# Modulo_Sensores.net
KiCad netlist of a schematic drawn in Altium Designer
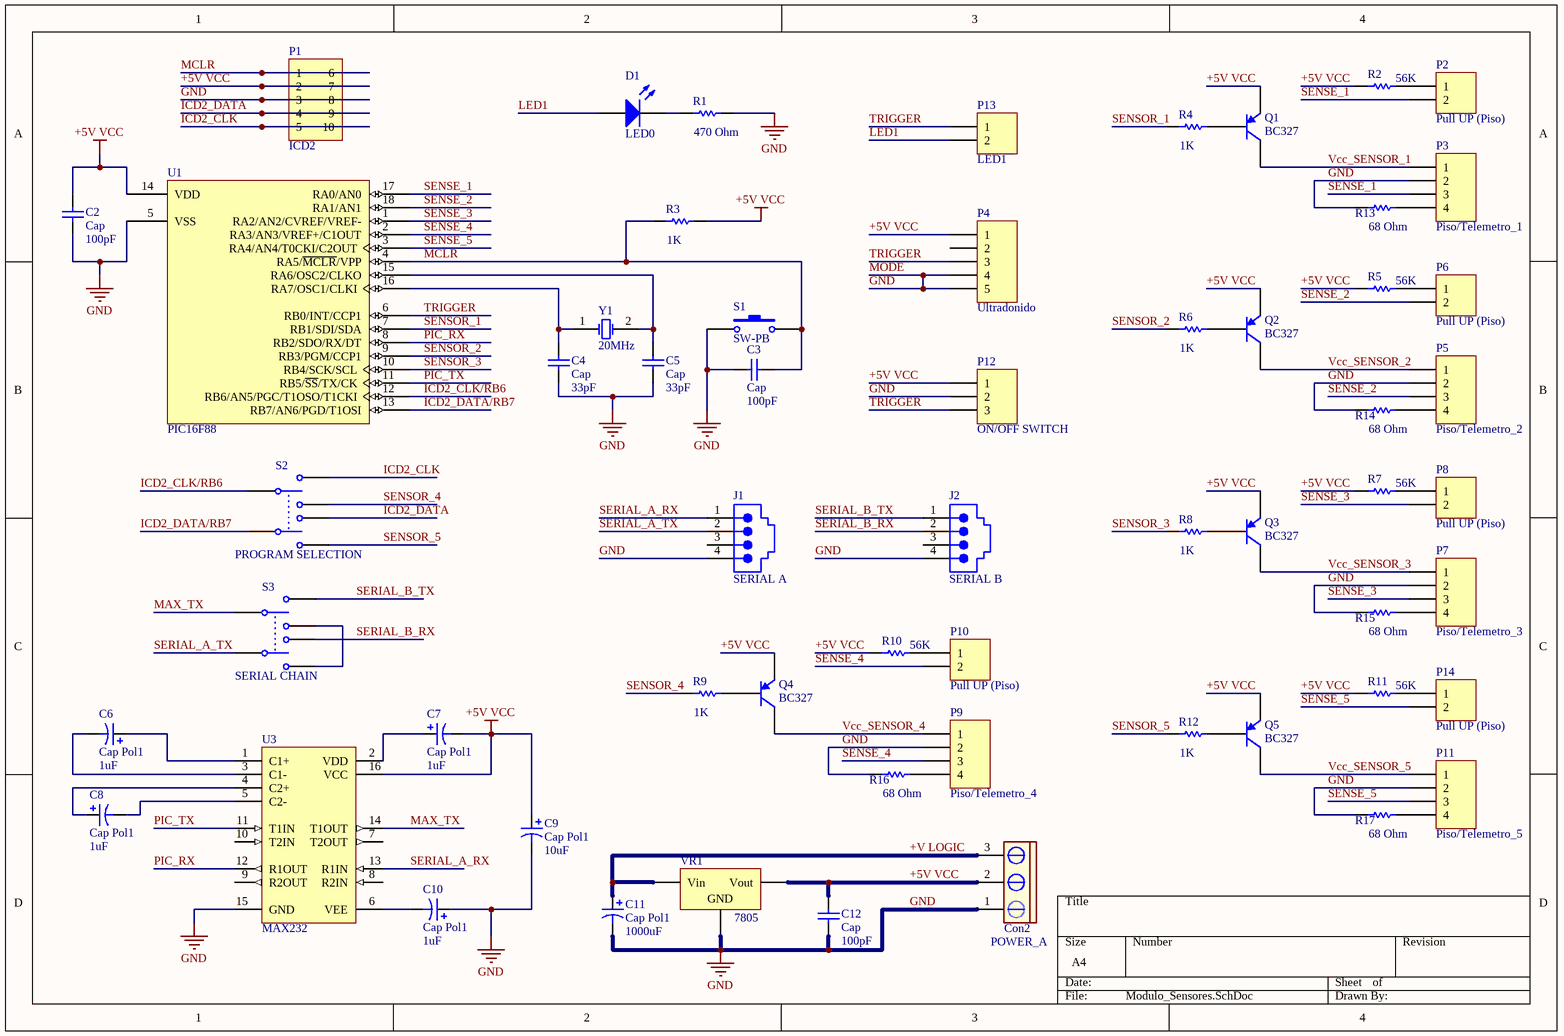
[diagram p0: Modulo_Sensores.SchDoc]

(export (version "E")
  (design (tool "Eeschema 10.0.6"))
  (components
    (comp (ref "C2")
      (value "Cap")
      (footprint "CAPR2.54-5.1x3.2")
      (description "Capacitor")
      (fields (field (name "ALTIUM_VALUE") "100pF") (field (name "PUBLISHER") "Altium Limited"))
      (libsource (lib "Miscellaneous Devices") (part "Cap"))
    )
    (comp (ref "C3")
      (value "Cap")
      (footprint "CAPR2.54-5.1x3.2")
      (description "Capacitor")
      (fields (field (name "ALTIUM_VALUE") "100pF") (field (name "PUBLISHER") "Altium Limited"))
      (libsource (lib "Miscellaneous Devices") (part "Cap"))
    )
    (comp (ref "C4")
      (value "Cap")
      (footprint "CAPR2.54-5.1x3.2")
      (description "Capacitor")
      (fields (field (name "ALTIUM_VALUE") "33pF") (field (name "PUBLISHER") "Altium Limited"))
      (libsource (lib "Miscellaneous Devices") (part "Cap"))
    )
    (comp (ref "C5")
      (value "Cap")
      (footprint "CAPR2.54-5.1x3.2")
      (description "Capacitor")
      (fields (field (name "ALTIUM_VALUE") "33pF") (field (name "PUBLISHER") "Altium Limited"))
      (libsource (lib "Miscellaneous Devices") (part "Cap"))
    )
    (comp (ref "C6")
      (value "Cap Pol1")
      (footprint "CAPPR2-5x6.8")
      (description "Polarized Capacitor (Radial)")
      (fields (field (name "ALTIUM_VALUE") "1uF") (field (name "PUBLISHER") "Altium Limited"))
      (libsource (lib "Miscellaneous Devices") (part "Cap Pol1"))
    )
    (comp (ref "C7")
      (value "Cap Pol1")
      (footprint "CAPPR2-5x6.8")
      (description "Polarized Capacitor (Radial)")
      (fields (field (name "ALTIUM_VALUE") "1uF") (field (name "PUBLISHER") "Altium Limited"))
      (libsource (lib "Miscellaneous Devices") (part "Cap Pol1"))
    )
    (comp (ref "C8")
      (value "Cap Pol1")
      (footprint "CAPPR2-5x6.8")
      (description "Polarized Capacitor (Radial)")
      (fields (field (name "ALTIUM_VALUE") "1uF") (field (name "PUBLISHER") "Altium Limited"))
      (libsource (lib "Miscellaneous Devices") (part "Cap Pol1"))
    )
    (comp (ref "C9")
      (value "Cap Pol1")
      (footprint "CAPPR2-5x6.8")
      (description "Polarized Capacitor (Radial)")
      (fields (field (name "ALTIUM_VALUE") "10uF") (field (name "PUBLISHER") "Altium Limited"))
      (libsource (lib "Miscellaneous Devices") (part "Cap Pol1"))
    )
    (comp (ref "C10")
      (value "Cap Pol1")
      (footprint "CAPPR2-5x6.8")
      (description "Polarized Capacitor (Radial)")
      (fields (field (name "ALTIUM_VALUE") "1uF") (field (name "PUBLISHER") "Altium Limited"))
      (libsource (lib "Miscellaneous Devices") (part "Cap Pol1"))
    )
    (comp (ref "C11")
      (value "Cap Pol1")
      (footprint "RB5-10.5")
      (description "Polarized Capacitor (Radial)")
      (fields (field (name "ALTIUM_VALUE") "1000uF") (field (name "PUBLISHER") "Altium Limited"))
      (libsource (lib "Miscellaneous Devices") (part "Cap Pol1"))
    )
    (comp (ref "C12")
      (value "Cap")
      (footprint "CAPR2.54-5.1x3.2")
      (description "Capacitor")
      (fields (field (name "ALTIUM_VALUE") "100pF") (field (name "PUBLISHER") "Altium Limited"))
      (libsource (lib "Miscellaneous Devices") (part "Cap"))
    )
    (comp (ref "Con2")
      (value "POWER_A")
      (footprint "My_CN3")
      (description "Connector green screw")
      (libsource (lib "Protel_Library") (part "CON3 pin Green"))
    )
    (comp (ref "D1")
      (value "LED0")
      (footprint "LED-0")
      (description "Typical INFRARED GaAs LED")
      (fields (field (name "PUBLISHER") "Altium Limited"))
      (libsource (lib "Miscellaneous Devices") (part "LED0"))
    )
    (comp (ref "J1")
      (value "SERIAL A")
      (footprint "15-43-6245")
      (description "Right Angle, Standard Profile, RJ45-Keyed, Flange Mount PCB Jack")
      (fields (field (name "PUBLISHER") "Altium Limited"))
      (libsource (lib "Molex Modular Jack Right Angle") (part "15-43-6245"))
    )
    (comp (ref "J2")
      (value "SERIAL B")
      (footprint "15-43-6245")
      (description "Right Angle, Standard Profile, RJ45-Keyed, Flange Mount PCB Jack")
      (fields (field (name "PUBLISHER") "Altium Limited"))
      (libsource (lib "Molex Modular Jack Right Angle") (part "15-43-6245"))
    )
    (comp (ref "P1")
      (value "ICD2")
      (footprint "HEADER10_5x2_B")
      (description "Header, 5-Pin, Dual row")
      (fields (field (name "PUBLISHER") "Altium Limited"))
      (libsource (lib "Miscellaneous Connectors") (part "Header 5X2A"))
    )
    (comp (ref "P2")
      (value "Pull UP (Piso)")
      (footprint "HDR1X2")
      (description "Header, 2-Pin")
      (fields (field (name "PUBLISHER") "Altium Limited"))
      (libsource (lib "Miscellaneous Connectors") (part "Header 2"))
    )
    (comp (ref "P3")
      (value "Piso/Telemetro_1")
      (footprint "HDR1X4")
      (description "Header, 4-Pin")
      (fields (field (name "PUBLISHER") "Altium Limited"))
      (libsource (lib "Miscellaneous Connectors") (part "Header 4"))
    )
    (comp (ref "P4")
      (value "Ultradonido")
      (footprint "HDR1X5")
      (description "Header, 5-Pin")
      (fields (field (name "PUBLISHER") "Altium Limited"))
      (libsource (lib "Miscellaneous Connectors") (part "Header 5"))
    )
    (comp (ref "P5")
      (value "Piso/Telemetro_2")
      (footprint "HDR1X4")
      (description "Header, 4-Pin")
      (fields (field (name "PUBLISHER") "Altium Limited"))
      (libsource (lib "Miscellaneous Connectors") (part "Header 4"))
    )
    (comp (ref "P6")
      (value "Pull UP (Piso)")
      (footprint "HDR1X2")
      (description "Header, 2-Pin")
      (fields (field (name "PUBLISHER") "Altium Limited"))
      (libsource (lib "Miscellaneous Connectors") (part "Header 2"))
    )
    (comp (ref "P7")
      (value "Piso/Telemetro_3")
      (footprint "HDR1X4")
      (description "Header, 4-Pin")
      (fields (field (name "PUBLISHER") "Altium Limited"))
      (libsource (lib "Miscellaneous Connectors") (part "Header 4"))
    )
    (comp (ref "P8")
      (value "Pull UP (Piso)")
      (footprint "HDR1X2")
      (description "Header, 2-Pin")
      (fields (field (name "PUBLISHER") "Altium Limited"))
      (libsource (lib "Miscellaneous Connectors") (part "Header 2"))
    )
    (comp (ref "P9")
      (value "Piso/Telemetro_4")
      (footprint "HDR1X4")
      (description "Header, 4-Pin")
      (fields (field (name "PUBLISHER") "Altium Limited"))
      (libsource (lib "Miscellaneous Connectors") (part "Header 4"))
    )
    (comp (ref "P10")
      (value "Pull UP (Piso)")
      (footprint "HDR1X2")
      (description "Header, 2-Pin")
      (fields (field (name "PUBLISHER") "Altium Limited"))
      (libsource (lib "Miscellaneous Connectors") (part "Header 2"))
    )
    (comp (ref "P11")
      (value "Piso/Telemetro_5")
      (footprint "HDR1X4")
      (description "Header, 4-Pin")
      (fields (field (name "PUBLISHER") "Altium Limited"))
      (libsource (lib "Miscellaneous Connectors") (part "Header 4"))
    )
    (comp (ref "P12")
      (value "ON/OFF SWITCH")
      (footprint "HDR1X3")
      (description "Header, 3-Pin")
      (fields (field (name "PUBLISHER") "Altium Limited"))
      (libsource (lib "Miscellaneous Connectors") (part "Header 3"))
    )
    (comp (ref "P13")
      (value "LED1")
      (footprint "HDR1X2")
      (description "Header, 2-Pin")
      (fields (field (name "PUBLISHER") "Altium Limited"))
      (libsource (lib "Miscellaneous Connectors") (part "Header 2"))
    )
    (comp (ref "P14")
      (value "Pull UP (Piso)")
      (footprint "HDR1X2")
      (description "Header, 2-Pin")
      (fields (field (name "PUBLISHER") "Altium Limited"))
      (libsource (lib "Miscellaneous Connectors") (part "Header 2"))
    )
    (comp (ref "Q1")
      (value "BC327")
      (footprint "TO-92A")
      (description "PNP Switching Transistor")
      (fields (field (name "PUBLISHER") "Altium Limited"))
      (libsource (lib "FSC Discrete BJT") (part "2N5771"))
    )
    (comp (ref "Q2")
      (value "BC327")
      (footprint "TO-92A")
      (description "PNP Switching Transistor")
      (fields (field (name "PUBLISHER") "Altium Limited"))
      (libsource (lib "FSC Discrete BJT") (part "2N5771"))
    )
    (comp (ref "Q3")
      (value "BC327")
      (footprint "TO-92A")
      (description "PNP Switching Transistor")
      (fields (field (name "PUBLISHER") "Altium Limited"))
      (libsource (lib "FSC Discrete BJT") (part "2N5771"))
    )
    (comp (ref "Q4")
      (value "BC327")
      (footprint "TO-92A")
      (description "PNP Switching Transistor")
      (fields (field (name "PUBLISHER") "Altium Limited"))
      (libsource (lib "FSC Discrete BJT") (part "2N5771"))
    )
    (comp (ref "Q5")
      (value "BC327")
      (footprint "TO-92A")
      (description "PNP Switching Transistor")
      (fields (field (name "PUBLISHER") "Altium Limited"))
      (libsource (lib "FSC Discrete BJT") (part "2N5771"))
    )
    (comp (ref "R1")
      (value "470 Ohm")
      (footprint "AXIAL-0.3")
      (description "Resistor")
      (fields (field (name "Comment") "Res1") (field (name "PUBLISHER") "Altium Limited"))
      (libsource (lib "Miscellaneous Devices") (part "Res1"))
    )
    (comp (ref "R2")
      (value "56K")
      (footprint "AXIAL-0.3")
      (description "Resistor")
      (fields (field (name "Comment") "Res1") (field (name "PUBLISHER") "Altium Limited"))
      (libsource (lib "Miscellaneous Devices") (part "Res1"))
    )
    (comp (ref "R3")
      (value "1K")
      (footprint "AXIAL-0.3")
      (description "Resistor")
      (fields (field (name "Comment") "Res1") (field (name "PUBLISHER") "Altium Limited"))
      (libsource (lib "Miscellaneous Devices") (part "Res1"))
    )
    (comp (ref "R4")
      (value "1K")
      (footprint "AXIAL-0.3")
      (description "Resistor")
      (fields (field (name "Comment") "Res1") (field (name "PUBLISHER") "Altium Limited"))
      (libsource (lib "Miscellaneous Devices") (part "Res1"))
    )
    (comp (ref "R5")
      (value "56K")
      (footprint "AXIAL-0.3")
      (description "Resistor")
      (fields (field (name "Comment") "Res1") (field (name "PUBLISHER") "Altium Limited"))
      (libsource (lib "Miscellaneous Devices") (part "Res1"))
    )
    (comp (ref "R6")
      (value "1K")
      (footprint "AXIAL-0.3")
      (description "Resistor")
      (fields (field (name "Comment") "Res1") (field (name "PUBLISHER") "Altium Limited"))
      (libsource (lib "Miscellaneous Devices") (part "Res1"))
    )
    (comp (ref "R7")
      (value "56K")
      (footprint "AXIAL-0.3")
      (description "Resistor")
      (fields (field (name "Comment") "Res1") (field (name "PUBLISHER") "Altium Limited"))
      (libsource (lib "Miscellaneous Devices") (part "Res1"))
    )
    (comp (ref "R8")
      (value "1K")
      (footprint "AXIAL-0.3")
      (description "Resistor")
      (fields (field (name "Comment") "Res1") (field (name "PUBLISHER") "Altium Limited"))
      (libsource (lib "Miscellaneous Devices") (part "Res1"))
    )
    (comp (ref "R9")
      (value "1K")
      (footprint "AXIAL-0.3")
      (description "Resistor")
      (fields (field (name "Comment") "Res1") (field (name "PUBLISHER") "Altium Limited"))
      (libsource (lib "Miscellaneous Devices") (part "Res1"))
    )
    (comp (ref "R10")
      (value "56K")
      (footprint "AXIAL-0.3")
      (description "Resistor")
      (fields (field (name "Comment") "Res1") (field (name "PUBLISHER") "Altium Limited"))
      (libsource (lib "Miscellaneous Devices") (part "Res1"))
    )
    (comp (ref "R11")
      (value "56K")
      (footprint "AXIAL-0.3")
      (description "Resistor")
      (fields (field (name "Comment") "Res1") (field (name "PUBLISHER") "Altium Limited"))
      (libsource (lib "Miscellaneous Devices") (part "Res1"))
    )
    (comp (ref "R12")
      (value "1K")
      (footprint "AXIAL-0.3")
      (description "Resistor")
      (fields (field (name "Comment") "Res1") (field (name "PUBLISHER") "Altium Limited"))
      (libsource (lib "Miscellaneous Devices") (part "Res1"))
    )
    (comp (ref "R13")
      (value "68 Ohm")
      (footprint "AXIAL-0.3")
      (description "Resistor")
      (fields (field (name "Comment") "Res1") (field (name "PUBLISHER") "Altium Limited"))
      (libsource (lib "Miscellaneous Devices") (part "Res1"))
    )
    (comp (ref "R14")
      (value "68 Ohm")
      (footprint "AXIAL-0.3")
      (description "Resistor")
      (fields (field (name "Comment") "Res1") (field (name "PUBLISHER") "Altium Limited"))
      (libsource (lib "Miscellaneous Devices") (part "Res1"))
    )
    (comp (ref "R15")
      (value "68 Ohm")
      (footprint "AXIAL-0.3")
      (description "Resistor")
      (fields (field (name "Comment") "Res1") (field (name "PUBLISHER") "Altium Limited"))
      (libsource (lib "Miscellaneous Devices") (part "Res1"))
    )
    (comp (ref "R16")
      (value "68 Ohm")
      (footprint "AXIAL-0.3")
      (description "Resistor")
      (fields (field (name "Comment") "Res1") (field (name "PUBLISHER") "Altium Limited"))
      (libsource (lib "Miscellaneous Devices") (part "Res1"))
    )
    (comp (ref "R17")
      (value "68 Ohm")
      (footprint "AXIAL-0.3")
      (description "Resistor")
      (fields (field (name "Comment") "Res1") (field (name "PUBLISHER") "Altium Limited"))
      (libsource (lib "Miscellaneous Devices") (part "Res1"))
    )
    (comp (ref "S1")
      (value "SW-PB")
      (footprint "TS-063")
      (description "Switch")
      (fields (field (name "PUBLISHER") "Altium Limited"))
      (libsource (lib "Miscellaneous Devices") (part "SW-PB"))
    )
    (comp (ref "S2")
      (value "PROGRAM SELECTION")
      (footprint "LD-202mini")
      (description "Double-Pole, Double-Throw Switch")
      (fields (field (name "PUBLISHER") "Altium Limited"))
      (libsource (lib "Miscellaneous Devices") (part "SW-DPDT"))
    )
    (comp (ref "S3")
      (value "SERIAL CHAIN")
      (footprint "LD-202mini")
      (description "Double-Pole, Double-Throw Switch")
      (fields (field (name "PUBLISHER") "Altium Limited"))
      (libsource (lib "Miscellaneous Devices") (part "SW-DPDT"))
    )
    (comp (ref "U1")
      (value "PIC16F88")
      (footprint "PDIP300-P18")
      (fields (field (name "PUBLISHER") "Altium Limited"))
      (libsource (lib "Microchip Microcontroller 8-Bit PIC16") (part "PIC16F88-E/P"))
    )
    (comp (ref "U3")
      (value "MAX232")
      (footprint "PE16A")
      (description "+5V Powered, Multi-Channel RS-232 Driver/Receiver")
      (fields (field (name "PUBLISHER") "Altium Limited"))
      (libsource (lib "Maxim Communication Transceiver") (part "MAX232ACPE"))
    )
    (comp (ref "VR1")
      (value "7805")
      (footprint "My_TO-220")
      (description "Voltage Regulator")
      (fields (field (name "PUBLISHER") "Altium Limited"))
      (libsource (lib "Miscellaneous Devices") (part "Volt Reg"))
    )
    (comp (ref "Y1")
      (value "20MHz")
      (footprint "My_Crystal")
      (description "Crystal Oscillator")
      (fields (field (name "PUBLISHER") "Altium Limited"))
      (libsource (lib "Miscellaneous Devices") (part "XTAL"))
    )
  )
  (nets
    (net (code "1") (name "+5V VCC") (class "Default")
      (node (ref "C12") (pin "2") (pinfunction "2_2") (pintype "passive"))
      (node (ref "C2") (pin "2") (pinfunction "2_2") (pintype "passive"))
      (node (ref "C7") (pin "2") (pinfunction "2_2") (pintype "passive"))
      (node (ref "C9") (pin "1") (pinfunction "1_1") (pintype "passive"))
      (node (ref "Con2") (pin "2") (pinfunction "2_2") (pintype "passive"))
      (node (ref "P1") (pin "2") (pinfunction "2_2") (pintype "passive"))
      (node (ref "P1") (pin "7") (pinfunction "7_7") (pintype "passive"))
      (node (ref "P12") (pin "1") (pinfunction "1_1") (pintype "passive"))
      (node (ref "P4") (pin "1") (pinfunction "1_1") (pintype "passive"))
      (node (ref "Q1") (pin "1") (pinfunction "E_1") (pintype "passive"))
      (node (ref "Q2") (pin "1") (pinfunction "E_1") (pintype "passive"))
      (node (ref "Q3") (pin "1") (pinfunction "E_1") (pintype "passive"))
      (node (ref "Q4") (pin "1") (pinfunction "E_1") (pintype "passive"))
      (node (ref "Q5") (pin "1") (pinfunction "E_1") (pintype "passive"))
      (node (ref "R10") (pin "1") (pinfunction "1_1") (pintype "passive"))
      (node (ref "R11") (pin "1") (pinfunction "1_1") (pintype "passive"))
      (node (ref "R2") (pin "1") (pinfunction "1_1") (pintype "passive"))
      (node (ref "R3") (pin "2") (pinfunction "2_2") (pintype "passive"))
      (node (ref "R5") (pin "1") (pinfunction "1_1") (pintype "passive"))
      (node (ref "R7") (pin "1") (pinfunction "1_1") (pintype "passive"))
      (node (ref "U1") (pin "14") (pinfunction "VDD_14") (pintype "power_in"))
      (node (ref "U3") (pin "16") (pinfunction "VCC_16") (pintype "power_in"))
      (node (ref "VR1") (pin "3") (pinfunction "Vout_3") (pintype "passive"))
    )
    (net (code "2") (name "/+V LOGIC") (class "Default")
      (node (ref "C11") (pin "1") (pinfunction "1_1") (pintype "passive"))
      (node (ref "Con2") (pin "3") (pinfunction "3_3") (pintype "passive"))
      (node (ref "VR1") (pin "1") (pinfunction "Vin_1") (pintype "passive"))
    )
    (net (code "3") (name "/ICD2_CLK") (class "Default")
      (node (ref "P1") (pin "10") (pinfunction "10_10") (pintype "passive"))
      (node (ref "P1") (pin "5") (pinfunction "5_5") (pintype "passive"))
      (node (ref "S2") (pin "2") (pinfunction "2_2") (pintype "passive"))
    )
    (net (code "4") (name "/ICD2_CLK{slash}RB6") (class "Default")
      (node (ref "S2") (pin "1") (pinfunction "1_1") (pintype "passive"))
      (node (ref "U1") (pin "12") (pinfunction "RB6/AN5/PGC/T1OSO/T1CKI_12") (pintype "bidirectional"))
    )
    (net (code "5") (name "/ICD2_DATA") (class "Default")
      (node (ref "P1") (pin "4") (pinfunction "4_4") (pintype "passive"))
      (node (ref "P1") (pin "9") (pinfunction "9_9") (pintype "passive"))
      (node (ref "S2") (pin "5") (pinfunction "5_5") (pintype "passive"))
    )
    (net (code "6") (name "/ICD2_DATA{slash}RB7") (class "Default")
      (node (ref "S2") (pin "4") (pinfunction "4_4") (pintype "passive"))
      (node (ref "U1") (pin "13") (pinfunction "RB7/AN6/PGD/T1OSI_13") (pintype "bidirectional"))
    )
    (net (code "7") (name "/LED1") (class "Default")
      (node (ref "D1") (pin "1") (pinfunction "A_1") (pintype "passive"))
      (node (ref "P13") (pin "2") (pinfunction "2_2") (pintype "passive"))
    )
    (net (code "8") (name "/MAX_TX") (class "Default")
      (node (ref "S3") (pin "1") (pinfunction "1_1") (pintype "passive"))
      (node (ref "U3") (pin "14") (pinfunction "T1OUT_14") (pintype "output"))
    )
    (net (code "9") (name "/MCLR") (class "Default")
      (node (ref "C3") (pin "2") (pinfunction "2_2") (pintype "passive"))
      (node (ref "P1") (pin "1") (pinfunction "1_1") (pintype "passive"))
      (node (ref "P1") (pin "6") (pinfunction "6_6") (pintype "passive"))
      (node (ref "R3") (pin "1") (pinfunction "1_1") (pintype "passive"))
      (node (ref "S1") (pin "2") (pinfunction "2_2") (pintype "passive"))
      (node (ref "U1") (pin "4") (pinfunction "RA5/~{MCLR}/VPP_4") (pintype "bidirectional"))
    )
    (net (code "10") (name "/PIC_RX") (class "Default")
      (node (ref "U1") (pin "8") (pinfunction "RB2/SDO/RX/DT_8") (pintype "bidirectional"))
      (node (ref "U3") (pin "12") (pinfunction "R1OUT_12") (pintype "output"))
    )
    (net (code "11") (name "/PIC_TX") (class "Default")
      (node (ref "U1") (pin "11") (pinfunction "RB5/~{SS}/TX/CK_11") (pintype "bidirectional"))
      (node (ref "U3") (pin "11") (pinfunction "T1IN_11") (pintype "input"))
    )
    (net (code "12") (name "/SENSE_1") (class "Default")
      (node (ref "P2") (pin "2") (pinfunction "2_2") (pintype "passive"))
      (node (ref "P3") (pin "3") (pinfunction "3_3") (pintype "passive"))
      (node (ref "U1") (pin "17") (pinfunction "RA0/AN0_17") (pintype "bidirectional"))
    )
    (net (code "13") (name "/SENSE_2") (class "Default")
      (node (ref "P5") (pin "3") (pinfunction "3_3") (pintype "passive"))
      (node (ref "P6") (pin "2") (pinfunction "2_2") (pintype "passive"))
      (node (ref "U1") (pin "18") (pinfunction "RA1/AN1_18") (pintype "bidirectional"))
    )
    (net (code "14") (name "/SENSE_3") (class "Default")
      (node (ref "P7") (pin "3") (pinfunction "3_3") (pintype "passive"))
      (node (ref "P8") (pin "2") (pinfunction "2_2") (pintype "passive"))
      (node (ref "U1") (pin "1") (pinfunction "RA2/AN2/CVREF/VREF-_1") (pintype "bidirectional"))
    )
    (net (code "15") (name "/SENSE_4") (class "Default")
      (node (ref "P10") (pin "2") (pinfunction "2_2") (pintype "passive"))
      (node (ref "P9") (pin "3") (pinfunction "3_3") (pintype "passive"))
      (node (ref "U1") (pin "2") (pinfunction "RA3/AN3/VREF+/C1OUT_2") (pintype "bidirectional"))
    )
    (net (code "16") (name "/SENSE_5") (class "Default")
      (node (ref "P11") (pin "3") (pinfunction "3_3") (pintype "passive"))
      (node (ref "P14") (pin "2") (pinfunction "2_2") (pintype "passive"))
      (node (ref "U1") (pin "3") (pinfunction "RA4/AN4/T0CKI/C2OUT_3") (pintype "bidirectional"))
    )
    (net (code "17") (name "/SENSOR_1") (class "Default")
      (node (ref "R4") (pin "1") (pinfunction "1_1") (pintype "passive"))
      (node (ref "U1") (pin "7") (pinfunction "RB1/SDI/SDA_7") (pintype "bidirectional"))
    )
    (net (code "18") (name "/SENSOR_2") (class "Default")
      (node (ref "R6") (pin "1") (pinfunction "1_1") (pintype "passive"))
      (node (ref "U1") (pin "9") (pinfunction "RB3/PGM/CCP1_9") (pintype "bidirectional"))
    )
    (net (code "19") (name "/SENSOR_3") (class "Default")
      (node (ref "R8") (pin "1") (pinfunction "1_1") (pintype "passive"))
      (node (ref "U1") (pin "10") (pinfunction "RB4/SCK/SCL_10") (pintype "bidirectional"))
    )
    (net (code "20") (name "/SENSOR_4") (class "Default")
      (node (ref "R9") (pin "1") (pinfunction "1_1") (pintype "passive"))
      (node (ref "S2") (pin "3") (pinfunction "3_3") (pintype "passive"))
    )
    (net (code "21") (name "/SENSOR_5") (class "Default")
      (node (ref "R12") (pin "1") (pinfunction "1_1") (pintype "passive"))
      (node (ref "S2") (pin "6") (pinfunction "6_6") (pintype "passive"))
    )
    (net (code "22") (name "/SERIAL_A_RX") (class "Default")
      (node (ref "J1") (pin "1") (pinfunction "1_1") (pintype "passive"))
      (node (ref "U3") (pin "13") (pinfunction "R1IN_13") (pintype "input"))
    )
    (net (code "23") (name "/SERIAL_A_TX") (class "Default")
      (node (ref "J1") (pin "2") (pinfunction "2_2") (pintype "passive"))
      (node (ref "S3") (pin "4") (pinfunction "4_4") (pintype "passive"))
    )
    (net (code "24") (name "/SERIAL_B_RX") (class "Default")
      (node (ref "J2") (pin "2") (pinfunction "2_2") (pintype "passive"))
      (node (ref "S3") (pin "5") (pinfunction "5_5") (pintype "passive"))
    )
    (net (code "25") (name "/SERIAL_B_TX") (class "Default")
      (node (ref "J2") (pin "1") (pinfunction "1_1") (pintype "passive"))
      (node (ref "S3") (pin "2") (pinfunction "2_2") (pintype "passive"))
    )
    (net (code "26") (name "/TRIGGER") (class "Default")
      (node (ref "P12") (pin "3") (pinfunction "3_3") (pintype "passive"))
      (node (ref "P13") (pin "1") (pinfunction "1_1") (pintype "passive"))
      (node (ref "P4") (pin "3") (pinfunction "3_3") (pintype "passive"))
      (node (ref "U1") (pin "6") (pinfunction "RB0/INT/CCP1_6") (pintype "bidirectional"))
    )
    (net (code "27") (name "/Vcc_SENSOR_1") (class "Default")
      (node (ref "P3") (pin "1") (pinfunction "1_1") (pintype "passive"))
      (node (ref "Q1") (pin "3") (pinfunction "C_3") (pintype "passive"))
    )
    (net (code "28") (name "/Vcc_SENSOR_2") (class "Default")
      (node (ref "P5") (pin "1") (pinfunction "1_1") (pintype "passive"))
      (node (ref "Q2") (pin "3") (pinfunction "C_3") (pintype "passive"))
    )
    (net (code "29") (name "/Vcc_SENSOR_3") (class "Default")
      (node (ref "P7") (pin "1") (pinfunction "1_1") (pintype "passive"))
      (node (ref "Q3") (pin "3") (pinfunction "C_3") (pintype "passive"))
    )
    (net (code "30") (name "/Vcc_SENSOR_4") (class "Default")
      (node (ref "P9") (pin "1") (pinfunction "1_1") (pintype "passive"))
      (node (ref "Q4") (pin "3") (pinfunction "C_3") (pintype "passive"))
    )
    (net (code "31") (name "/Vcc_SENSOR_5") (class "Default")
      (node (ref "P11") (pin "1") (pinfunction "1_1") (pintype "passive"))
      (node (ref "Q5") (pin "3") (pinfunction "C_3") (pintype "passive"))
    )
    (net (code "32") (name "GND") (class "Default")
      (node (ref "C10") (pin "1") (pinfunction "1_1") (pintype "passive"))
      (node (ref "C11") (pin "2") (pinfunction "2_2") (pintype "passive"))
      (node (ref "C12") (pin "1") (pinfunction "1_1") (pintype "passive"))
      (node (ref "C2") (pin "1") (pinfunction "1_1") (pintype "passive"))
      (node (ref "C3") (pin "1") (pinfunction "1_1") (pintype "passive"))
      (node (ref "C4") (pin "1") (pinfunction "1_1") (pintype "passive"))
      (node (ref "C5") (pin "1") (pinfunction "1_1") (pintype "passive"))
      (node (ref "C9") (pin "2") (pinfunction "2_2") (pintype "passive"))
      (node (ref "Con2") (pin "1") (pinfunction "1_1") (pintype "passive"))
      (node (ref "J1") (pin "4") (pinfunction "4_4") (pintype "passive"))
      (node (ref "J2") (pin "4") (pinfunction "4_4") (pintype "passive"))
      (node (ref "P1") (pin "3") (pinfunction "3_3") (pintype "passive"))
      (node (ref "P1") (pin "8") (pinfunction "8_8") (pintype "passive"))
      (node (ref "P11") (pin "2") (pinfunction "2_2") (pintype "passive"))
      (node (ref "P12") (pin "2") (pinfunction "2_2") (pintype "passive"))
      (node (ref "P3") (pin "2") (pinfunction "2_2") (pintype "passive"))
      (node (ref "P4") (pin "4") (pinfunction "4_4") (pintype "passive"))
      (node (ref "P4") (pin "5") (pinfunction "5_5") (pintype "passive"))
      (node (ref "P5") (pin "2") (pinfunction "2_2") (pintype "passive"))
      (node (ref "P7") (pin "2") (pinfunction "2_2") (pintype "passive"))
      (node (ref "P9") (pin "2") (pinfunction "2_2") (pintype "passive"))
      (node (ref "R1") (pin "2") (pinfunction "2_2") (pintype "passive"))
      (node (ref "R13") (pin "1") (pinfunction "1_1") (pintype "passive"))
      (node (ref "R14") (pin "1") (pinfunction "1_1") (pintype "passive"))
      (node (ref "R15") (pin "1") (pinfunction "1_1") (pintype "passive"))
      (node (ref "R16") (pin "1") (pinfunction "1_1") (pintype "passive"))
      (node (ref "R17") (pin "1") (pinfunction "1_1") (pintype "passive"))
      (node (ref "S1") (pin "1") (pinfunction "1_1") (pintype "passive"))
      (node (ref "U1") (pin "5") (pinfunction "VSS_5") (pintype "power_in"))
      (node (ref "U3") (pin "15") (pinfunction "GND_15") (pintype "power_in"))
      (node (ref "VR1") (pin "2") (pinfunction "GND_2") (pintype "passive"))
    )
    (net (code "33") (name "Net-(D1-K)") (class "Default")
      (node (ref "D1") (pin "2") (pinfunction "K_2") (pintype "passive"))
      (node (ref "R1") (pin "1") (pinfunction "1_1") (pintype "passive"))
    )
    (net (code "34") (name "Net-(P2-Pad1)") (class "Default")
      (node (ref "P2") (pin "1") (pinfunction "1_1") (pintype "passive"))
      (node (ref "R2") (pin "2") (pinfunction "2_2") (pintype "passive"))
    )
    (net (code "35") (name "Net-(P3-Pad4)") (class "Default")
      (node (ref "P3") (pin "4") (pinfunction "4_4") (pintype "passive"))
      (node (ref "R13") (pin "2") (pinfunction "2_2") (pintype "passive"))
    )
    (net (code "36") (name "Net-(P5-Pad4)") (class "Default")
      (node (ref "P5") (pin "4") (pinfunction "4_4") (pintype "passive"))
      (node (ref "R14") (pin "2") (pinfunction "2_2") (pintype "passive"))
    )
    (net (code "37") (name "Net-(P6-Pad1)") (class "Default")
      (node (ref "P6") (pin "1") (pinfunction "1_1") (pintype "passive"))
      (node (ref "R5") (pin "2") (pinfunction "2_2") (pintype "passive"))
    )
    (net (code "38") (name "Net-(P7-Pad4)") (class "Default")
      (node (ref "P7") (pin "4") (pinfunction "4_4") (pintype "passive"))
      (node (ref "R15") (pin "2") (pinfunction "2_2") (pintype "passive"))
    )
    (net (code "39") (name "Net-(P8-Pad1)") (class "Default")
      (node (ref "P8") (pin "1") (pinfunction "1_1") (pintype "passive"))
      (node (ref "R7") (pin "2") (pinfunction "2_2") (pintype "passive"))
    )
    (net (code "40") (name "Net-(P9-Pad4)") (class "Default")
      (node (ref "P9") (pin "4") (pinfunction "4_4") (pintype "passive"))
      (node (ref "R16") (pin "2") (pinfunction "2_2") (pintype "passive"))
    )
    (net (code "41") (name "Net-(P10-Pad1)") (class "Default")
      (node (ref "P10") (pin "1") (pinfunction "1_1") (pintype "passive"))
      (node (ref "R10") (pin "2") (pinfunction "2_2") (pintype "passive"))
    )
    (net (code "42") (name "Net-(P11-Pad4)") (class "Default")
      (node (ref "P11") (pin "4") (pinfunction "4_4") (pintype "passive"))
      (node (ref "R17") (pin "2") (pinfunction "2_2") (pintype "passive"))
    )
    (net (code "43") (name "Net-(P14-Pad1)") (class "Default")
      (node (ref "P14") (pin "1") (pinfunction "1_1") (pintype "passive"))
      (node (ref "R11") (pin "2") (pinfunction "2_2") (pintype "passive"))
    )
    (net (code "44") (name "Net-(Q1-B)") (class "Default")
      (node (ref "Q1") (pin "2") (pinfunction "B_2") (pintype "passive"))
      (node (ref "R4") (pin "2") (pinfunction "2_2") (pintype "passive"))
    )
    (net (code "45") (name "Net-(Q2-B)") (class "Default")
      (node (ref "Q2") (pin "2") (pinfunction "B_2") (pintype "passive"))
      (node (ref "R6") (pin "2") (pinfunction "2_2") (pintype "passive"))
    )
    (net (code "46") (name "Net-(Q3-B)") (class "Default")
      (node (ref "Q3") (pin "2") (pinfunction "B_2") (pintype "passive"))
      (node (ref "R8") (pin "2") (pinfunction "2_2") (pintype "passive"))
    )
    (net (code "47") (name "Net-(Q4-B)") (class "Default")
      (node (ref "Q4") (pin "2") (pinfunction "B_2") (pintype "passive"))
      (node (ref "R9") (pin "2") (pinfunction "2_2") (pintype "passive"))
    )
    (net (code "48") (name "Net-(Q5-B)") (class "Default")
      (node (ref "Q5") (pin "2") (pinfunction "B_2") (pintype "passive"))
      (node (ref "R12") (pin "2") (pinfunction "2_2") (pintype "passive"))
    )
    (net (code "49") (name "Net-(S3-Pad3)") (class "Default")
      (node (ref "S3") (pin "3") (pinfunction "3_3") (pintype "passive"))
      (node (ref "S3") (pin "6") (pinfunction "6_6") (pintype "passive"))
    )
    (net (code "50") (name "Net-(U1-RA6{slash}OSC2{slash}CLKO)") (class "Default")
      (node (ref "C5") (pin "2") (pinfunction "2_2") (pintype "passive"))
      (node (ref "U1") (pin "15") (pinfunction "RA6/OSC2/CLKO_15") (pintype "bidirectional"))
      (node (ref "Y1") (pin "2") (pinfunction "OSC2_2") (pintype "passive"))
    )
    (net (code "51") (name "Net-(U1-RA7{slash}OSC1{slash}CLKI)") (class "Default")
      (node (ref "C4") (pin "2") (pinfunction "2_2") (pintype "passive"))
      (node (ref "U1") (pin "16") (pinfunction "RA7/OSC1/CLKI_16") (pintype "bidirectional"))
      (node (ref "Y1") (pin "1") (pinfunction "OSC1_1") (pintype "passive"))
    )
    (net (code "52") (name "Net-(U3-C1+)") (class "Default")
      (node (ref "C6") (pin "1") (pinfunction "1_1") (pintype "passive"))
      (node (ref "U3") (pin "1") (pinfunction "C1+_1") (pintype "passive"))
    )
    (net (code "53") (name "Net-(U3-C1-)") (class "Default")
      (node (ref "C6") (pin "2") (pinfunction "2_2") (pintype "passive"))
      (node (ref "U3") (pin "3") (pinfunction "C1-_3") (pintype "passive"))
    )
    (net (code "54") (name "Net-(U3-C2+)") (class "Default")
      (node (ref "C8") (pin "1") (pinfunction "1_1") (pintype "passive"))
      (node (ref "U3") (pin "4") (pinfunction "C2+_4") (pintype "passive"))
    )
    (net (code "55") (name "Net-(U3-C2-)") (class "Default")
      (node (ref "C8") (pin "2") (pinfunction "2_2") (pintype "passive"))
      (node (ref "U3") (pin "5") (pinfunction "C2-_5") (pintype "passive"))
    )
    (net (code "56") (name "Net-(U3-VDD)") (class "Default")
      (node (ref "C7") (pin "1") (pinfunction "1_1") (pintype "passive"))
      (node (ref "U3") (pin "2") (pinfunction "VDD_2") (pintype "power_in"))
    )
    (net (code "57") (name "Net-(U3-VEE)") (class "Default")
      (node (ref "C10") (pin "2") (pinfunction "2_2") (pintype "passive"))
      (node (ref "U3") (pin "6") (pinfunction "VEE_6") (pintype "power_in"))
    )
    (net (code "58") (name "unconnected-(J1-Pad3)") (class "Default")
      (node (ref "J1") (pin "3") (pinfunction "3_3") (pintype "passive"))
    )
    (net (code "59") (name "unconnected-(J2-Pad3)") (class "Default")
      (node (ref "J2") (pin "3") (pinfunction "3_3") (pintype "passive"))
    )
    (net (code "60") (name "unconnected-(P4-Pad2)") (class "Default")
      (node (ref "P4") (pin "2") (pinfunction "2_2") (pintype "passive"))
    )
    (net (code "61") (name "unconnected-(U3-R2IN-Pad8)") (class "Default")
      (node (ref "U3") (pin "8") (pinfunction "R2IN_8") (pintype "input"))
    )
    (net (code "62") (name "unconnected-(U3-R2OUT-Pad9)") (class "Default")
      (node (ref "U3") (pin "9") (pinfunction "R2OUT_9") (pintype "output"))
    )
    (net (code "63") (name "unconnected-(U3-T2IN-Pad10)") (class "Default")
      (node (ref "U3") (pin "10") (pinfunction "T2IN_10") (pintype "input"))
    )
    (net (code "64") (name "unconnected-(U3-T2OUT-Pad7)") (class "Default")
      (node (ref "U3") (pin "7") (pinfunction "T2OUT_7") (pintype "output"))
    )
  )
)
